# power.net
KiCad netlist of a schematic drawn in Altium Designer
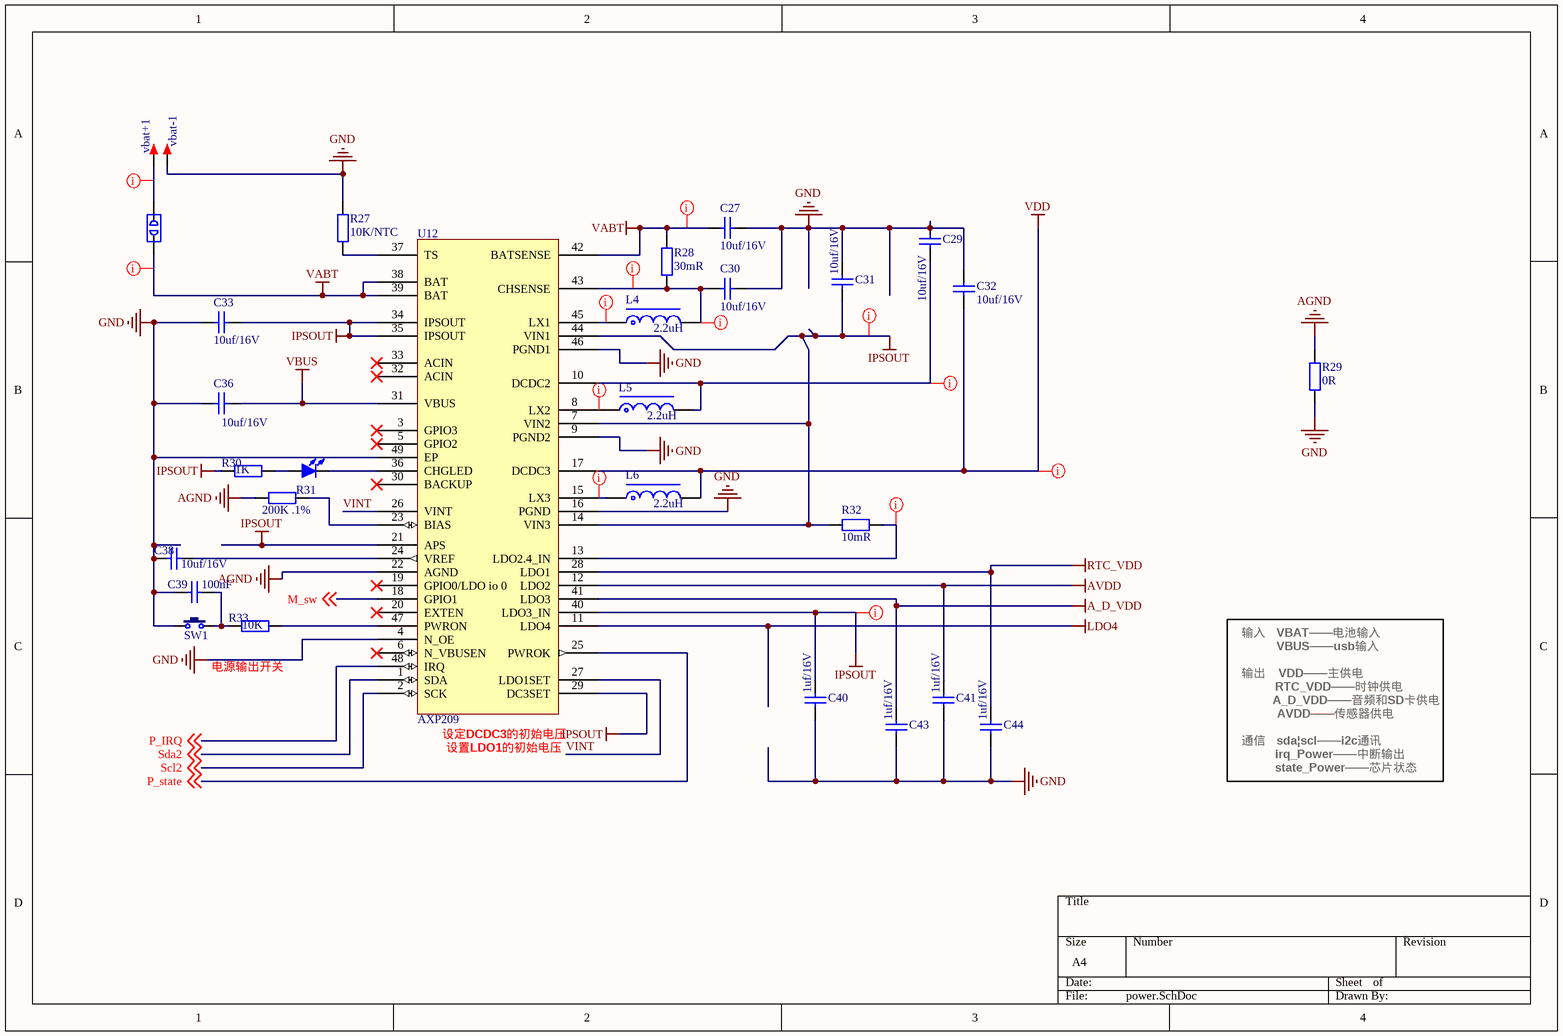
[diagram p0: power.SchDoc]

(export (version "E")
  (design (tool "Eeschema 10.0.6"))
  (components
    (comp (ref "C27")
      (value "10uf/16V")
      (footprint "C 0603_L")
      (description "贴片电容")
      (libsource (lib "0.1 - 电阻-电容-电感") (part "C"))
    )
    (comp (ref "C29")
      (value "10uf/16V")
      (footprint "C 0603_L")
      (description "贴片电容")
      (libsource (lib "0.1 - 电阻-电容-电感") (part "C"))
    )
    (comp (ref "C30")
      (value "10uf/16V")
      (footprint "C 0603_L")
      (description "贴片电容")
      (libsource (lib "0.1 - 电阻-电容-电感") (part "C"))
    )
    (comp (ref "C31")
      (value "10uf/16V")
      (footprint "C 0603_L")
      (description "贴片电容")
      (libsource (lib "0.1 - 电阻-电容-电感") (part "C"))
    )
    (comp (ref "C32")
      (value "10uf/16V")
      (footprint "C 0603_L")
      (description "贴片电容")
      (libsource (lib "0.1 - 电阻-电容-电感") (part "C"))
    )
    (comp (ref "C33")
      (value "10uf/16V")
      (footprint "C 0603_L")
      (description "贴片电容")
      (libsource (lib "0.1 - 电阻-电容-电感") (part "C"))
    )
    (comp (ref "C36")
      (value "10uf/16V")
      (footprint "C 0603_L")
      (description "贴片电容")
      (libsource (lib "0.1 - 电阻-电容-电感") (part "C"))
    )
    (comp (ref "C38")
      (value "10uf/16V")
      (footprint "C 0603_L")
      (description "贴片电容")
      (libsource (lib "0.1 - 电阻-电容-电感") (part "C"))
    )
    (comp (ref "C39")
      (value "100nF")
      (footprint "C 0603_L")
      (description "贴片电容")
      (libsource (lib "0.1 - 电阻-电容-电感") (part "C"))
    )
    (comp (ref "C40")
      (value "1uf/16V")
      (footprint "C 0603_L")
      (description "贴片电容")
      (libsource (lib "0.1 - 电阻-电容-电感") (part "C"))
    )
    (comp (ref "C41")
      (value "1uf/16V")
      (footprint "C 0603_L")
      (description "贴片电容")
      (libsource (lib "0.1 - 电阻-电容-电感") (part "C"))
    )
    (comp (ref "C43")
      (value "1uf/16V")
      (footprint "C 0603_L")
      (description "贴片电容")
      (libsource (lib "0.1 - 电阻-电容-电感") (part "C"))
    )
    (comp (ref "C44")
      (value "1uf/16V")
      (footprint "C 0603_L")
      (description "贴片电容")
      (libsource (lib "0.1 - 电阻-电容-电感") (part "C"))
    )
    (comp (ref "DE2")
      (value "DEBUG PAD")
      (footprint "DEBUG_B")
      (description "调试断点焊盘")
      (libsource (lib "0.7 - 常用按键-开关-蜂鸣器-电池") (part "DEBUG"))
    )
    (comp (ref "L4")
      (value "2.2uH")
      (footprint "NR2520")
      (description "NR磁胶电感")
      (libsource (lib "0.1 - 电阻-电容-电感") (part "L-NR"))
    )
    (comp (ref "L5")
      (value "2.2uH")
      (footprint "NR2520")
      (description "NR磁胶电感")
      (libsource (lib "0.1 - 电阻-电容-电感") (part "L-NR"))
    )
    (comp (ref "L6")
      (value "2.2uH")
      (footprint "NR2520")
      (description "NR磁胶电感")
      (libsource (lib "0.1 - 电阻-电容-电感") (part "L-NR"))
    )
    (comp (ref "LED1")
      (value "红色")
      (footprint "LED 0603W")
      (description "贴片LED")
      (libsource (lib "0.3 - LED发光二极管") (part "LED-SMD"))
    )
    (comp (ref "R27")
      (value "10K/NTC")
      (footprint "R 0603_L")
      (description "贴片电阻")
      (libsource (lib "0.1 - 电阻-电容-电感") (part "R"))
    )
    (comp (ref "R28")
      (value "30mR")
      (footprint "R 0805_L")
      (description "贴片电阻")
      (libsource (lib "0.1 - 电阻-电容-电感") (part "R"))
    )
    (comp (ref "R29")
      (value "0R")
      (footprint "R 0603_L")
      (description "贴片电阻")
      (libsource (lib "0.1 - 电阻-电容-电感") (part "R"))
    )
    (comp (ref "R30")
      (value "1K")
      (footprint "R 0603_L")
      (description "贴片电阻")
      (libsource (lib "0.1 - 电阻-电容-电感") (part "R"))
    )
    (comp (ref "R31")
      (value "200K .1%")
      (footprint "R 0603_L")
      (description "贴片电阻")
      (libsource (lib "0.1 - 电阻-电容-电感") (part "R"))
    )
    (comp (ref "R32")
      (value "10mR")
      (footprint "R 0805_L")
      (description "贴片电阻")
      (libsource (lib "0.1 - 电阻-电容-电感") (part "R"))
    )
    (comp (ref "R33")
      (value "10K")
      (footprint "R 0603_L")
      (description "贴片电阻")
      (libsource (lib "0.1 - 电阻-电容-电感") (part "R"))
    )
    (comp (ref "SW1")
      (value "3x6x5")
      (footprint "TSW 3*6*4.3-S-W")
      (description "3x6轻触开关")
      (libsource (lib "0.7 - 常用按键-开关-蜂鸣器-电池") (part "TSW 3x6"))
    )
    (comp (ref "U12")
      (value "AXP209")
      (footprint "QFN-48_L6.0-W6.0-P0.40-TL-EP4.2")
      (libsource (lib "1.1 - 电源类芯片") (part "AXP209"))
    )
    (comp (ref "vbat+1")
      (value "TEST")
      (footprint "TEST 1.6")
      (description "测试点")
      (libsource (lib "0.7 - 常用按键-开关-蜂鸣器-电池") (part "TEST"))
    )
    (comp (ref "vbat-1")
      (value "TEST")
      (footprint "TEST 1.6")
      (description "测试点")
      (libsource (lib "0.7 - 常用按键-开关-蜂鸣器-电池") (part "TEST"))
    )
  )
  (nets
    (net (code "1") (name "/VINT") (class "Default")
      (node (ref "U12") (pin "26") (pinfunction "VINT_26") (pintype "passive"))
      (node (ref "U12") (pin "27") (pinfunction "LDO1SET_27") (pintype "passive"))
    )
    (net (code "2") (name "AGND") (class "Default")
      (node (ref "R29") (pin "2") (pinfunction "2_2") (pintype "passive"))
      (node (ref "R31") (pin "1") (pinfunction "1_1") (pintype "passive"))
      (node (ref "U12") (pin "22") (pinfunction "AGND_22") (pintype "passive"))
    )
    (net (code "3") (name "AVDD") (class "Default")
      (node (ref "C41") (pin "1") (pinfunction "1_1") (pintype "passive"))
      (node (ref "U12") (pin "12") (pinfunction "LDO2_12") (pintype "power_in"))
    )
    (net (code "4") (name "A_D_VDD") (class "Default")
      (node (ref "C43") (pin "1") (pinfunction "1_1") (pintype "passive"))
      (node (ref "U12") (pin "41") (pinfunction "LDO3_41") (pintype "power_in"))
    )
    (net (code "5") (name "GND") (class "Default")
      (node (ref "C27") (pin "1") (pinfunction "1_1") (pintype "passive"))
      (node (ref "C29") (pin "1") (pinfunction "1_1") (pintype "passive"))
      (node (ref "C30") (pin "1") (pinfunction "1_1") (pintype "passive"))
      (node (ref "C31") (pin "1") (pinfunction "1_1") (pintype "passive"))
      (node (ref "C32") (pin "1") (pinfunction "1_1") (pintype "passive"))
      (node (ref "C33") (pin "2") (pinfunction "2_2") (pintype "passive"))
      (node (ref "C36") (pin "1") (pinfunction "1_1") (pintype "passive"))
      (node (ref "C38") (pin "1") (pinfunction "1_1") (pintype "passive"))
      (node (ref "C39") (pin "1") (pinfunction "1_1") (pintype "passive"))
      (node (ref "C40") (pin "2") (pinfunction "2_2") (pintype "passive"))
      (node (ref "C41") (pin "2") (pinfunction "2_2") (pintype "passive"))
      (node (ref "C43") (pin "2") (pinfunction "2_2") (pintype "passive"))
      (node (ref "C44") (pin "2") (pinfunction "2_2") (pintype "passive"))
      (node (ref "R27") (pin "1") (pinfunction "1_1") (pintype "passive"))
      (node (ref "R29") (pin "1") (pinfunction "1_1") (pintype "passive"))
      (node (ref "SW1") (pin "1") (pinfunction "1_1") (pintype "passive"))
      (node (ref "U12") (pin "16") (pinfunction "PGND_16") (pintype "power_in"))
      (node (ref "U12") (pin "4") (pinfunction "N_OE_4") (pintype "passive"))
      (node (ref "U12") (pin "46") (pinfunction "PGND1_46") (pintype "power_in"))
      (node (ref "U12") (pin "49") (pinfunction "EP_49") (pintype "passive"))
      (node (ref "U12") (pin "9") (pinfunction "PGND2_9") (pintype "power_in"))
      (node (ref "vbat-1") (pin "1") (pinfunction "1_1") (pintype "passive"))
    )
    (net (code "6") (name "IPSOUT") (class "Default")
      (node (ref "C31") (pin "2") (pinfunction "2_2") (pintype "passive"))
      (node (ref "C33") (pin "1") (pinfunction "1_1") (pintype "passive"))
      (node (ref "C40") (pin "1") (pinfunction "1_1") (pintype "passive"))
      (node (ref "R30") (pin "1") (pinfunction "1_1") (pintype "passive"))
      (node (ref "R32") (pin "1") (pinfunction "1_1") (pintype "passive"))
      (node (ref "U12") (pin "14") (pinfunction "VIN3_14") (pintype "power_in"))
      (node (ref "U12") (pin "21") (pinfunction "APS_21") (pintype "passive"))
      (node (ref "U12") (pin "29") (pinfunction "DC3SET_29") (pintype "passive"))
      (node (ref "U12") (pin "34") (pinfunction "IPSOUT_34") (pintype "passive"))
      (node (ref "U12") (pin "35") (pinfunction "IPSOUT_35") (pintype "passive"))
      (node (ref "U12") (pin "40") (pinfunction "LDO3_IN_40") (pintype "power_in"))
      (node (ref "U12") (pin "44") (pinfunction "VIN1_44") (pintype "power_in"))
      (node (ref "U12") (pin "7") (pinfunction "VIN2_7") (pintype "power_in"))
    )
    (net (code "7") (name "LDO4") (class "Default")
      (node (ref "U12") (pin "11") (pinfunction "LDO4_11") (pintype "power_in"))
    )
    (net (code "8") (name "M_sw") (class "Default")
      (node (ref "U12") (pin "18") (pinfunction "GPIO1_18") (pintype "passive"))
    )
    (net (code "9") (name "Net-(C39-Pad2)") (class "Default")
      (node (ref "C39") (pin "2") (pinfunction "2_2") (pintype "passive"))
      (node (ref "R33") (pin "1") (pinfunction "1_1") (pintype "passive"))
      (node (ref "SW1") (pin "2") (pinfunction "2_2") (pintype "passive"))
    )
    (net (code "10") (name "Net-(DE2-Pad1)") (class "Default")
      (node (ref "DE2") (pin "1") (pinfunction "1_1") (pintype "passive"))
      (node (ref "vbat+1") (pin "1") (pinfunction "1_1") (pintype "passive"))
    )
    (net (code "11") (name "Net-(LED1-A)") (class "Default")
      (node (ref "LED1") (pin "1") (pinfunction "A_1") (pintype "passive"))
      (node (ref "R30") (pin "2") (pinfunction "2_2") (pintype "passive"))
    )
    (net (code "12") (name "Net-(LED1-K)") (class "Default")
      (node (ref "LED1") (pin "2") (pinfunction "K_2") (pintype "passive"))
      (node (ref "U12") (pin "36") (pinfunction "CHGLED_36") (pintype "passive"))
    )
    (net (code "13") (name "Net-(U12-BIAS)") (class "Default")
      (node (ref "R31") (pin "2") (pinfunction "2_2") (pintype "passive"))
      (node (ref "U12") (pin "23") (pinfunction "BIAS_23") (pintype "bidirectional"))
    )
    (net (code "14") (name "Net-(U12-CHSENSE)") (class "Default")
      (node (ref "C30") (pin "2") (pinfunction "2_2") (pintype "passive"))
      (node (ref "L4") (pin "2") (pinfunction "2_2") (pintype "passive"))
      (node (ref "R28") (pin "1") (pinfunction "1_1") (pintype "passive"))
      (node (ref "U12") (pin "43") (pinfunction "CHSENSE_43") (pintype "power_in"))
    )
    (net (code "15") (name "Net-(U12-DCDC2)") (class "Default")
      (node (ref "C29") (pin "2") (pinfunction "2_2") (pintype "passive"))
      (node (ref "L5") (pin "2") (pinfunction "2_2") (pintype "passive"))
      (node (ref "U12") (pin "10") (pinfunction "DCDC2_10") (pintype "power_in"))
    )
    (net (code "16") (name "Net-(U12-LDO2.4_IN)") (class "Default")
      (node (ref "R32") (pin "2") (pinfunction "2_2") (pintype "passive"))
      (node (ref "U12") (pin "13") (pinfunction "LDO2.4_IN_13") (pintype "power_in"))
    )
    (net (code "17") (name "Net-(U12-LX1)") (class "Default")
      (node (ref "L4") (pin "1") (pinfunction "1_1") (pintype "passive"))
      (node (ref "U12") (pin "45") (pinfunction "LX1_45") (pintype "power_in"))
    )
    (net (code "18") (name "Net-(U12-LX2)") (class "Default")
      (node (ref "L5") (pin "1") (pinfunction "1_1") (pintype "passive"))
      (node (ref "U12") (pin "8") (pinfunction "LX2_8") (pintype "power_in"))
    )
    (net (code "19") (name "Net-(U12-LX3)") (class "Default")
      (node (ref "L6") (pin "1") (pinfunction "1_1") (pintype "passive"))
      (node (ref "U12") (pin "15") (pinfunction "LX3_15") (pintype "power_in"))
    )
    (net (code "20") (name "Net-(U12-PWRON)") (class "Default")
      (node (ref "R33") (pin "2") (pinfunction "2_2") (pintype "passive"))
      (node (ref "U12") (pin "47") (pinfunction "PWRON_47") (pintype "passive"))
    )
    (net (code "21") (name "Net-(U12-TS)") (class "Default")
      (node (ref "R27") (pin "2") (pinfunction "2_2") (pintype "passive"))
      (node (ref "U12") (pin "37") (pinfunction "TS_37") (pintype "passive"))
    )
    (net (code "22") (name "Net-(U12-VREF)") (class "Default")
      (node (ref "C38") (pin "2") (pinfunction "2_2") (pintype "passive"))
      (node (ref "U12") (pin "24") (pinfunction "VREF_24") (pintype "output"))
    )
    (net (code "23") (name "P_IRQ") (class "Default")
      (node (ref "U12") (pin "48") (pinfunction "IRQ_48") (pintype "bidirectional"))
    )
    (net (code "24") (name "P_state") (class "Default")
      (node (ref "U12") (pin "25") (pinfunction "PWROK_25") (pintype "output"))
    )
    (net (code "25") (name "RTC_VDD") (class "Default")
      (node (ref "C44") (pin "1") (pinfunction "1_1") (pintype "passive"))
      (node (ref "U12") (pin "28") (pinfunction "LDO1_28") (pintype "power_in"))
    )
    (net (code "26") (name "Scl2") (class "Default")
      (node (ref "U12") (pin "2") (pinfunction "SCK_2") (pintype "bidirectional"))
    )
    (net (code "27") (name "Sda2") (class "Default")
      (node (ref "U12") (pin "1") (pinfunction "SDA_1") (pintype "bidirectional"))
    )
    (net (code "28") (name "VABT") (class "Default")
      (node (ref "C27") (pin "2") (pinfunction "2_2") (pintype "passive"))
      (node (ref "DE2") (pin "2") (pinfunction "2_2") (pintype "passive"))
      (node (ref "R28") (pin "2") (pinfunction "2_2") (pintype "passive"))
      (node (ref "U12") (pin "38") (pinfunction "BAT_38") (pintype "power_in"))
      (node (ref "U12") (pin "39") (pinfunction "BAT_39") (pintype "power_in"))
      (node (ref "U12") (pin "42") (pinfunction "BATSENSE_42") (pintype "power_in"))
    )
    (net (code "29") (name "VBUS") (class "Default")
      (node (ref "C36") (pin "2") (pinfunction "2_2") (pintype "passive"))
      (node (ref "U12") (pin "31") (pinfunction "VBUS_31") (pintype "power_in"))
    )
    (net (code "30") (name "VDD") (class "Default")
      (node (ref "C32") (pin "2") (pinfunction "2_2") (pintype "passive"))
      (node (ref "L6") (pin "2") (pinfunction "2_2") (pintype "passive"))
      (node (ref "U12") (pin "17") (pinfunction "DCDC3_17") (pintype "power_in"))
    )
    (net (code "31") (name "unconnected-(U12-ACIN-Pad32)") (class "Default")
      (node (ref "U12") (pin "32") (pinfunction "ACIN_32") (pintype "power_in+no_connect"))
    )
    (net (code "32") (name "unconnected-(U12-ACIN-Pad33)") (class "Default")
      (node (ref "U12") (pin "33") (pinfunction "ACIN_33") (pintype "power_in+no_connect"))
    )
    (net (code "33") (name "unconnected-(U12-BACKUP-Pad30)") (class "Default")
      (node (ref "U12") (pin "30") (pinfunction "BACKUP_30") (pintype "passive+no_connect"))
    )
    (net (code "34") (name "unconnected-(U12-EXTEN-Pad20)") (class "Default")
      (node (ref "U12") (pin "20") (pinfunction "EXTEN_20") (pintype "passive+no_connect"))
    )
    (net (code "35") (name "unconnected-(U12-GPIO0{slash}LDO_io_0-Pad19)") (class "Default")
      (node (ref "U12") (pin "19") (pinfunction "GPIO0/LDO_io_0_19") (pintype "passive+no_connect"))
    )
    (net (code "36") (name "unconnected-(U12-GPIO2-Pad5)") (class "Default")
      (node (ref "U12") (pin "5") (pinfunction "GPIO2_5") (pintype "passive+no_connect"))
    )
    (net (code "37") (name "unconnected-(U12-GPIO3-Pad3)") (class "Default")
      (node (ref "U12") (pin "3") (pinfunction "GPIO3_3") (pintype "passive+no_connect"))
    )
    (net (code "38") (name "unconnected-(U12-N_VBUSEN-Pad6)") (class "Default")
      (node (ref "U12") (pin "6") (pinfunction "N_VBUSEN_6") (pintype "bidirectional+no_connect"))
    )
  )
)
